# Discharge_Load_Switch.net
KiCad netlist of a schematic drawn in Altium Designer
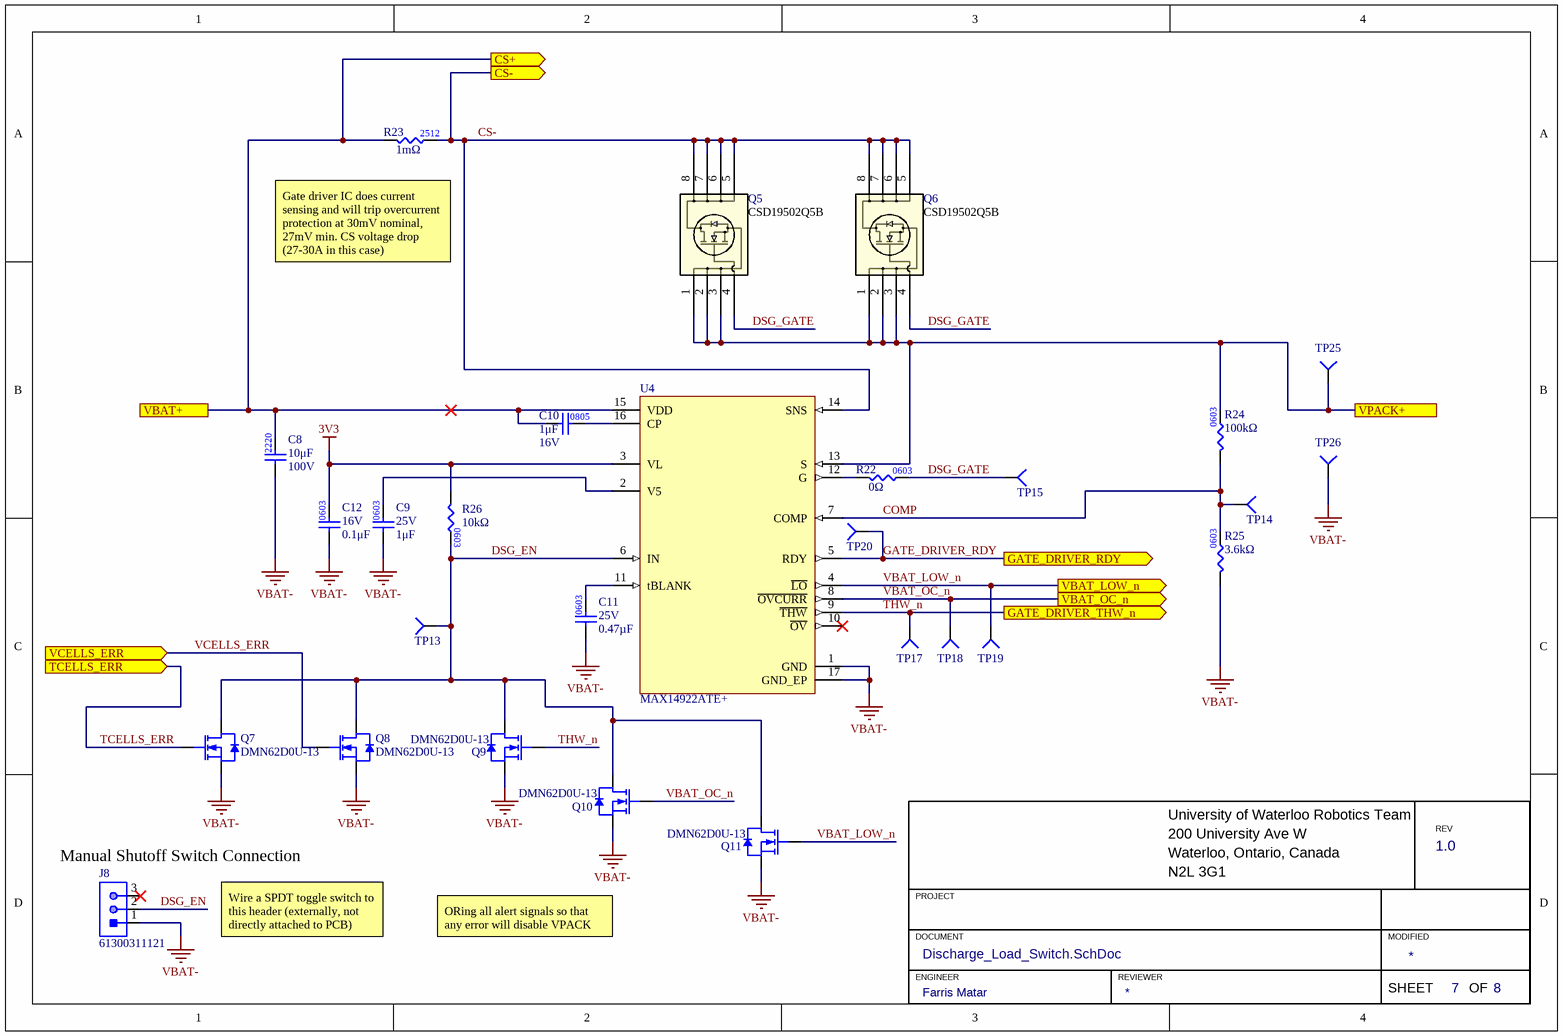
[diagram p0: Discharge_Load_Switch.SchDoc]

(export (version "E")
  (design (tool "Eeschema 10.0.6"))
  (components
    (comp (ref "C8")
      (value "10μF")
      (footprint "CAP2220")
      (description "CAP CER 10UF 100V X7S 2220")
      (fields (field (name "VOLTAGE RATING") "100V") (field (name "Comment") "CAP_10μF_100V_2220"))
      (libsource (lib "Personal_Schematic_Library_2022") (part "CAP_10μF_100V_2220"))
    )
    (comp (ref "C9")
      (value "1μF")
      (footprint "CAP0603")
      (description "CAP CER 1UF 25V X5R 0603")
      (fields (field (name "VOLTAGE RATING") "25V") (field (name "Comment") "CAP_1uF_25V_0603"))
      (libsource (lib "Personal_Schematic_Library_2022") (part "CAP_1uF_25V_0603"))
    )
    (comp (ref "C10")
      (value "1μF")
      (footprint "CAP0805")
      (description "CAP CER 1UF 16V X7R 0805")
      (fields (field (name "VOLTAGE RATING") "16V") (field (name "Comment") "CAP_1uF_16V_0805"))
      (libsource (lib "Personal_Schematic_Library_2022") (part "CAP_1uF_16V_0805"))
    )
    (comp (ref "C11")
      (value "0.47µF")
      (footprint "CAP0603")
      (description "CAP CER 0.47UF 25V X7R 0603")
      (fields (field (name "VOLTAGE RATING") "25V") (field (name "Comment") "CAP_0.47uF_25V_0603"))
      (libsource (lib "Personal_Schematic_Library_2022") (part "CAP_0.47uF_25V_0603"))
    )
    (comp (ref "C12")
      (value "0.1μF")
      (footprint "CAP0603")
      (description "CAP CER 0.1UF 16V X7R 0603")
      (fields (field (name "VOLTAGE RATING") "16V") (field (name "Comment") "CAP_0.1uF_16V_0603"))
      (libsource (lib "Personal_Schematic_Library_2022") (part "CAP_0.1uF_16V_0603"))
    )
    (comp (ref "J8")
      (value "HEADER 3x1")
      (footprint "HDR1X3")
      (description "CONN HEADER VERT 3POS 2.54MM")
      (fields (field (name "MANUFACTURER PART NUMBER 1") "61300311121"))
      (libsource (lib "Personal_Schematic_Library_2022") (part "HEADER 3x1"))
    )
    (comp (ref "Q5")
      (value "CSD19502Q5B")
      (footprint "DFN5060")
      (description "MOSFET N-CH 80V 100A 8VSON")
      (fields (field (name "MANUFACTURER PART NUMBER 1") "CSD19502Q5B"))
      (libsource (lib "Personal_Schematic_Library_2022") (part "NMOS_CSD19502Q5B_80V_100A"))
    )
    (comp (ref "Q6")
      (value "CSD19502Q5B")
      (footprint "DFN5060")
      (description "MOSFET N-CH 80V 100A 8VSON")
      (fields (field (name "MANUFACTURER PART NUMBER 1") "CSD19502Q5B"))
      (libsource (lib "Personal_Schematic_Library_2022") (part "NMOS_CSD19502Q5B_80V_100A"))
    )
    (comp (ref "Q7")
      (value "NMOS_60V_380mA")
      (footprint "NMOS_SSOT-3")
      (description "MOSFET N-CH 60V 380MA SOT23")
      (fields (field (name "MANUFACTURER PART NUMBER 1") "DMN62D0U-13"))
      (libsource (lib "Personal_Schematic_Library_2022") (part "NMOS_60V_380mA"))
    )
    (comp (ref "Q8")
      (value "NMOS_60V_380mA")
      (footprint "NMOS_SSOT-3")
      (description "MOSFET N-CH 60V 380MA SOT23")
      (fields (field (name "MANUFACTURER PART NUMBER 1") "DMN62D0U-13"))
      (libsource (lib "Personal_Schematic_Library_2022") (part "NMOS_60V_380mA"))
    )
    (comp (ref "Q9")
      (value "NMOS_60V_380mA")
      (footprint "NMOS_SSOT-3")
      (description "MOSFET N-CH 60V 380MA SOT23")
      (fields (field (name "MANUFACTURER PART NUMBER 1") "DMN62D0U-13"))
      (libsource (lib "Personal_Schematic_Library_2022") (part "NMOS_60V_380mA"))
    )
    (comp (ref "Q10")
      (value "NMOS_60V_380mA")
      (footprint "NMOS_SSOT-3")
      (description "MOSFET N-CH 60V 380MA SOT23")
      (fields (field (name "MANUFACTURER PART NUMBER 1") "DMN62D0U-13"))
      (libsource (lib "Personal_Schematic_Library_2022") (part "NMOS_60V_380mA"))
    )
    (comp (ref "Q11")
      (value "NMOS_60V_380mA")
      (footprint "NMOS_SSOT-3")
      (description "MOSFET N-CH 60V 380MA SOT23")
      (fields (field (name "MANUFACTURER PART NUMBER 1") "DMN62D0U-13"))
      (libsource (lib "Personal_Schematic_Library_2022") (part "NMOS_60V_380mA"))
    )
    (comp (ref "R22")
      (value "0Ω")
      (footprint "RES0603")
      (description "RES 0 OHM JUMPER 1/10W 0603")
      (fields (field (name "Comment") "RES_0Ω_0603"))
      (libsource (lib "Personal_Schematic_Library_2022") (part "RES_0Ω_0603"))
    )
    (comp (ref "R23")
      (value "1mΩ")
      (footprint "RESC6532X75N")
      (description "RES 1 mOHM 1% 3W 2512")
      (fields (field (name "Comment") "RES_1mΩ_2512_1%"))
      (libsource (lib "Personal_Schematic_Library_2022") (part "RES_1mΩ_2512_1%"))
    )
    (comp (ref "R24")
      (value "100kΩ")
      (footprint "RES0603")
      (description "RES 100K OHM 1% 1/10W 0603")
      (fields (field (name "Comment") "RES_100kΩ_0603_1%"))
      (libsource (lib "Personal_Schematic_Library_2022") (part "RES_100kΩ_0603_1%"))
    )
    (comp (ref "R25")
      (value "3.6kΩ")
      (footprint "RES0603")
      (description "RES 3.6K OHM 1% 1/10W 0603")
      (fields (field (name "Comment") "RES_3.6kΩ_0603_1%"))
      (libsource (lib "Personal_Schematic_Library_2022") (part "RES_3.6kΩ_0603_1%"))
    )
    (comp (ref "R26")
      (value "10kΩ")
      (footprint "RES0603")
      (description "RES 10K OHM 1% 1/8W 0603")
      (fields (field (name "Comment") "RES_10kΩ_0603_1%"))
      (libsource (lib "Personal_Schematic_Library_2022") (part "RES_10kΩ_0603_1%"))
    )
    (comp (ref "TP13")
      (value "TESTPOINT_1MM_CIRCLE")
      (footprint "TESTPOINT_CIRCLE_1MM")
      (description "TESTPOINT 1MM CIRCLE")
      (libsource (lib "Personal_Schematic_Library_2022") (part "TESTPOINT_1MM_CIRCLE"))
    )
    (comp (ref "TP14")
      (value "TESTPOINT_1MM_CIRCLE")
      (footprint "TESTPOINT_CIRCLE_1MM")
      (description "TESTPOINT 1MM CIRCLE")
      (libsource (lib "Personal_Schematic_Library_2022") (part "TESTPOINT_1MM_CIRCLE"))
    )
    (comp (ref "TP15")
      (value "TESTPOINT_1MM_CIRCLE")
      (footprint "TESTPOINT_CIRCLE_1MM")
      (description "TESTPOINT 1MM CIRCLE")
      (libsource (lib "Personal_Schematic_Library_2022") (part "TESTPOINT_1MM_CIRCLE"))
    )
    (comp (ref "TP17")
      (value "TESTPOINT_1MM_CIRCLE")
      (footprint "TESTPOINT_CIRCLE_1MM")
      (description "TESTPOINT 1MM CIRCLE")
      (libsource (lib "Personal_Schematic_Library_2022") (part "TESTPOINT_1MM_CIRCLE"))
    )
    (comp (ref "TP18")
      (value "TESTPOINT_1MM_CIRCLE")
      (footprint "TESTPOINT_CIRCLE_1MM")
      (description "TESTPOINT 1MM CIRCLE")
      (libsource (lib "Personal_Schematic_Library_2022") (part "TESTPOINT_1MM_CIRCLE"))
    )
    (comp (ref "TP19")
      (value "TESTPOINT_1MM_CIRCLE")
      (footprint "TESTPOINT_CIRCLE_1MM")
      (description "TESTPOINT 1MM CIRCLE")
      (libsource (lib "Personal_Schematic_Library_2022") (part "TESTPOINT_1MM_CIRCLE"))
    )
    (comp (ref "TP20")
      (value "TESTPOINT_1MM_CIRCLE")
      (footprint "TESTPOINT_CIRCLE_1MM")
      (description "TESTPOINT 1MM CIRCLE")
      (libsource (lib "Personal_Schematic_Library_2022") (part "TESTPOINT_1MM_CIRCLE"))
    )
    (comp (ref "TP25")
      (value "TESTPOINT_SMD_LOOP")
      (footprint "S1751-46R")
      (description "TESTPOINT SMD LOOP")
      (libsource (lib "UWRT_Schematic_Library_2020") (part "TESTPOINT_SMD_LOOP"))
    )
    (comp (ref "TP26")
      (value "TESTPOINT_SMD_LOOP")
      (footprint "S1751-46R")
      (description "TESTPOINT SMD LOOP")
      (libsource (lib "UWRT_Schematic_Library_2020") (part "TESTPOINT_SMD_LOOP"))
    )
    (comp (ref "U4")
      (value "MAX14922ATE+")
      (footprint "16-WFQFN MAXIM")
      (description "HIGH-SIDE SWITCH CONTROLLER")
      (libsource (lib "Personal_Schematic_Library_2022") (part "MAX14922ATE+"))
    )
  )
  (nets
    (net (code "1") (name "/COMP") (class "Default")
      (node (ref "R24") (pin "1") (pinfunction "1_1") (pintype "passive"))
      (node (ref "R25") (pin "2") (pinfunction "2_2") (pintype "passive"))
      (node (ref "TP14") (pin "1") (pinfunction "=value_1") (pintype "passive"))
      (node (ref "U4") (pin "7") (pinfunction "COMP_7") (pintype "input"))
    )
    (net (code "2") (name "/CS+") (class "Default")
      (node (ref "C10") (pin "1") (pinfunction "1_1") (pintype "passive"))
      (node (ref "C8") (pin "2") (pinfunction "2_2") (pintype "passive"))
      (node (ref "R23") (pin "1") (pinfunction "1_1") (pintype "passive"))
      (node (ref "U4") (pin "15") (pinfunction "VDD_15") (pintype "power_in"))
    )
    (net (code "3") (name "/CS-") (class "Default")
      (node (ref "Q5") (pin "5") (pinfunction "D_5") (pintype "passive"))
      (node (ref "Q5") (pin "6") (pinfunction "D_6") (pintype "passive"))
      (node (ref "Q5") (pin "7") (pinfunction "D_7") (pintype "passive"))
      (node (ref "Q5") (pin "8") (pinfunction "D_8") (pintype "passive"))
      (node (ref "Q6") (pin "5") (pinfunction "D_5") (pintype "passive"))
      (node (ref "Q6") (pin "6") (pinfunction "D_6") (pintype "passive"))
      (node (ref "Q6") (pin "7") (pinfunction "D_7") (pintype "passive"))
      (node (ref "Q6") (pin "8") (pinfunction "D_8") (pintype "passive"))
      (node (ref "R23") (pin "2") (pinfunction "2_2") (pintype "passive"))
      (node (ref "U4") (pin "14") (pinfunction "SNS_14") (pintype "input"))
    )
    (net (code "4") (name "/DSG_EN") (class "Default")
      (node (ref "J8") (pin "2") (pinfunction "2_2") (pintype "passive"))
      (node (ref "Q10") (pin "3") (pinfunction "DRAIN_3") (pintype "passive"))
      (node (ref "Q11") (pin "3") (pinfunction "DRAIN_3") (pintype "passive"))
      (node (ref "Q7") (pin "3") (pinfunction "DRAIN_3") (pintype "passive"))
      (node (ref "Q8") (pin "3") (pinfunction "DRAIN_3") (pintype "passive"))
      (node (ref "Q9") (pin "3") (pinfunction "DRAIN_3") (pintype "passive"))
      (node (ref "R26") (pin "2") (pinfunction "2_2") (pintype "passive"))
      (node (ref "TP13") (pin "1") (pinfunction "=value_1") (pintype "passive"))
      (node (ref "U4") (pin "6") (pinfunction "IN_6") (pintype "input"))
    )
    (net (code "5") (name "/DSG_GATE") (class "Default")
      (node (ref "Q5") (pin "4") (pinfunction "G_4") (pintype "passive"))
      (node (ref "Q6") (pin "4") (pinfunction "G_4") (pintype "passive"))
      (node (ref "R22") (pin "2") (pinfunction "2_2") (pintype "passive"))
      (node (ref "TP15") (pin "1") (pinfunction "=value_1") (pintype "passive"))
    )
    (net (code "6") (name "/GATE_DRIVER_RDY") (class "Default")
      (node (ref "TP20") (pin "1") (pinfunction "=value_1") (pintype "passive"))
      (node (ref "U4") (pin "5") (pinfunction "RDY_5") (pintype "output"))
    )
    (net (code "7") (name "/TCELLS_ERR") (class "Default")
      (node (ref "Q7") (pin "1") (pinfunction "GATE_1") (pintype "passive"))
    )
    (net (code "8") (name "/THW_n") (class "Default")
      (node (ref "Q9") (pin "1") (pinfunction "GATE_1") (pintype "passive"))
      (node (ref "TP17") (pin "1") (pinfunction "=value_1") (pintype "passive"))
      (node (ref "U4") (pin "9") (pinfunction "~{THW}_9") (pintype "output"))
    )
    (net (code "9") (name "/VBAT_LOW_n") (class "Default")
      (node (ref "Q11") (pin "1") (pinfunction "GATE_1") (pintype "passive"))
      (node (ref "TP19") (pin "1") (pinfunction "=value_1") (pintype "passive"))
      (node (ref "U4") (pin "4") (pinfunction "~{LO}_4") (pintype "output"))
    )
    (net (code "10") (name "/VBAT_OC_n") (class "Default")
      (node (ref "Q10") (pin "1") (pinfunction "GATE_1") (pintype "passive"))
      (node (ref "TP18") (pin "1") (pinfunction "=value_1") (pintype "passive"))
      (node (ref "U4") (pin "8") (pinfunction "~{OVCURR}_8") (pintype "output"))
    )
    (net (code "11") (name "/VCELLS_ERR") (class "Default")
      (node (ref "Q8") (pin "1") (pinfunction "GATE_1") (pintype "passive"))
    )
    (net (code "12") (name "/VPACK+") (class "Default")
      (node (ref "Q5") (pin "1") (pinfunction "S_1") (pintype "passive"))
      (node (ref "Q5") (pin "2") (pinfunction "S_2") (pintype "passive"))
      (node (ref "Q5") (pin "3") (pinfunction "S_3") (pintype "passive"))
      (node (ref "Q6") (pin "1") (pinfunction "S_1") (pintype "passive"))
      (node (ref "Q6") (pin "2") (pinfunction "S_2") (pintype "passive"))
      (node (ref "Q6") (pin "3") (pinfunction "S_3") (pintype "passive"))
      (node (ref "R24") (pin "2") (pinfunction "2_2") (pintype "passive"))
      (node (ref "TP25") (pin "1") (pinfunction "=value_1") (pintype "passive"))
      (node (ref "U4") (pin "13") (pinfunction "S_13") (pintype "input"))
    )
    (net (code "13") (name "3V3") (class "Default")
      (node (ref "C12") (pin "2") (pinfunction "2_2") (pintype "passive"))
      (node (ref "R26") (pin "1") (pinfunction "1_1") (pintype "passive"))
      (node (ref "U4") (pin "3") (pinfunction "VL_3") (pintype "power_in"))
    )
    (net (code "14") (name "Net-(U4-CP)") (class "Default")
      (node (ref "C10") (pin "2") (pinfunction "2_2") (pintype "passive"))
      (node (ref "U4") (pin "16") (pinfunction "CP_16") (pintype "power_in"))
    )
    (net (code "15") (name "Net-(U4-G)") (class "Default")
      (node (ref "R22") (pin "1") (pinfunction "1_1") (pintype "passive"))
      (node (ref "U4") (pin "12") (pinfunction "G_12") (pintype "output"))
    )
    (net (code "16") (name "Net-(U4-V5)") (class "Default")
      (node (ref "C9") (pin "2") (pinfunction "2_2") (pintype "passive"))
      (node (ref "U4") (pin "2") (pinfunction "V5_2") (pintype "power_in"))
    )
    (net (code "17") (name "Net-(U4-tBLANK)") (class "Default")
      (node (ref "C11") (pin "2") (pinfunction "2_2") (pintype "passive"))
      (node (ref "U4") (pin "11") (pinfunction "tBLANK_11") (pintype "input"))
    )
    (net (code "18") (name "VBAT-") (class "Default")
      (node (ref "C11") (pin "1") (pinfunction "1_1") (pintype "passive"))
      (node (ref "C12") (pin "1") (pinfunction "1_1") (pintype "passive"))
      (node (ref "C8") (pin "1") (pinfunction "1_1") (pintype "passive"))
      (node (ref "C9") (pin "1") (pinfunction "1_1") (pintype "passive"))
      (node (ref "J8") (pin "1") (pinfunction "1_1") (pintype "passive"))
      (node (ref "Q10") (pin "2") (pinfunction "SOURCE_2") (pintype "passive"))
      (node (ref "Q11") (pin "2") (pinfunction "SOURCE_2") (pintype "passive"))
      (node (ref "Q7") (pin "2") (pinfunction "SOURCE_2") (pintype "passive"))
      (node (ref "Q8") (pin "2") (pinfunction "SOURCE_2") (pintype "passive"))
      (node (ref "Q9") (pin "2") (pinfunction "SOURCE_2") (pintype "passive"))
      (node (ref "R25") (pin "1") (pinfunction "1_1") (pintype "passive"))
      (node (ref "TP26") (pin "1") (pinfunction "=value_1") (pintype "passive"))
      (node (ref "U4") (pin "1") (pinfunction "GND_1") (pintype "power_in"))
      (node (ref "U4") (pin "17") (pinfunction "GND_EP_17") (pintype "power_in"))
    )
    (net (code "19") (name "unconnected-(J8-Pad3)") (class "Default")
      (node (ref "J8") (pin "3") (pinfunction "3_3") (pintype "passive+no_connect"))
    )
    (net (code "20") (name "unconnected-(U4-~{OV}-Pad10)") (class "Default")
      (node (ref "U4") (pin "10") (pinfunction "~{OV}_10") (pintype "output+no_connect"))
    )
  )
)
